# alcometer.net
KiCad netlist of a schematic drawn in EAGLE
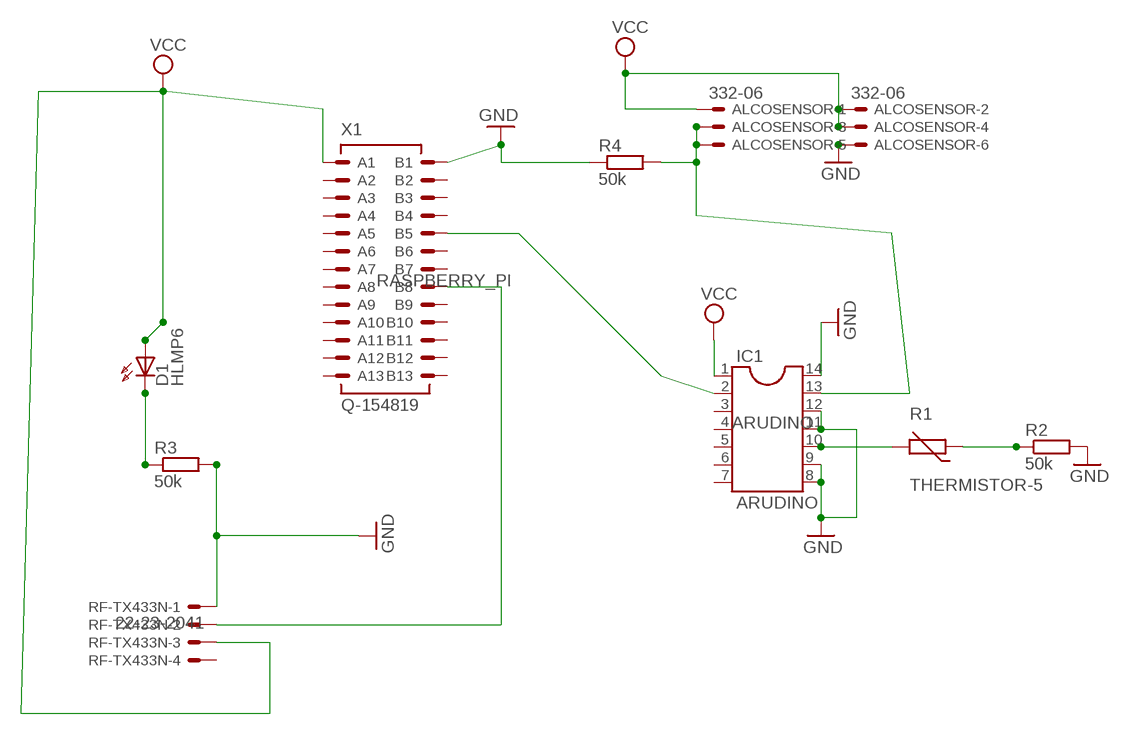
[diagram p0: schematic, sheet 1]

(export (version "E")
  (design (tool "Eeschema 10.0.6"))
  (components
    (comp (ref "ALCOSENSOR")
      (value "332-06")
      (footprint "eagle-import:332-06")
      (libsource (lib "eagle-import") (part "332-06"))
    )
    (comp (ref "D1")
      (value "HLMP6")
      (footprint "eagle-import:HLMP6")
      (fields (field (name "MF") "AGILENT TECHNOLOGIES") (field (name "MPN") "HLMP-6500"))
      (libsource (lib "eagle-import") (part "HLMP6"))
    )
    (comp (ref "IC1")
      (value "ARUDINO")
      (footprint "eagle-import:DIL14")
      (libsource (lib "eagle-import") (part "DIL14"))
    )
    (comp (ref "R1")
      (value "THERMISTOR-5")
      (footprint "eagle-import:R-5")
      (libsource (lib "eagle-import") (part "THERMISTOR-5"))
    )
    (comp (ref "R2")
      (value "50k")
      (footprint "eagle-import:0204_7")
      (libsource (lib "eagle-import") (part "R-EU_0204/7"))
    )
    (comp (ref "R3")
      (value "50k")
      (footprint "eagle-import:0204_7")
      (libsource (lib "eagle-import") (part "R-EU_0204/7"))
    )
    (comp (ref "R4")
      (value "50k")
      (footprint "eagle-import:0204_7")
      (libsource (lib "eagle-import") (part "R-EU_0204/7"))
    )
    (comp (ref "RF-TX433N")
      (value "22-23-2041")
      (footprint "eagle-import:22-23-2041")
      (fields (field (name "MF") "MOLEX"))
      (libsource (lib "eagle-import") (part "22-23-2041"))
    )
    (comp (ref "X1")
      (value "Q-154819")
      (footprint "eagle-import:154819")
      (libsource (lib "eagle-import") (part "Q-154819"))
    )
  )
  (nets
    (net (code "1") (name "GND") (class "Default")
      (node (ref "ALCOSENSOR") (pin "6") (pinfunction "S_6") (pintype "passive"))
      (node (ref "IC1") (pin "11") (pinfunction "11_11") (pintype "passive"))
      (node (ref "IC1") (pin "12") (pinfunction "12_12") (pintype "passive"))
      (node (ref "IC1") (pin "14") (pinfunction "14_14") (pintype "passive"))
      (node (ref "IC1") (pin "8") (pinfunction "8_8") (pintype "passive"))
      (node (ref "IC1") (pin "9") (pinfunction "9_9") (pintype "passive"))
      (node (ref "R2") (pin "2") (pinfunction "2_2") (pintype "passive"))
      (node (ref "R3") (pin "2") (pinfunction "2_2") (pintype "passive"))
      (node (ref "R4") (pin "1") (pinfunction "1_1") (pintype "passive"))
      (node (ref "RF-TX433N") (pin "1") (pinfunction "S_1") (pintype "passive"))
      (node (ref "X1") (pin "B1") (pinfunction "B1_B1") (pintype "passive"))
    )
    (net (code "2") (name "Net-(ALCOSENSORC-S)") (class "Default")
      (node (ref "ALCOSENSOR") (pin "3") (pinfunction "S_3") (pintype "passive"))
      (node (ref "ALCOSENSOR") (pin "5") (pinfunction "S_5") (pintype "passive"))
      (node (ref "IC1") (pin "13") (pinfunction "13_13") (pintype "passive"))
      (node (ref "R4") (pin "2") (pinfunction "2_2") (pintype "passive"))
    )
    (net (code "3") (name "Net-(D1-PadK)") (class "Default")
      (node (ref "D1") (pin "K") (pinfunction "K_K") (pintype "passive"))
      (node (ref "R3") (pin "1") (pinfunction "1_1") (pintype "passive"))
    )
    (net (code "4") (name "Net-(IC1-Pad2)") (class "Default")
      (node (ref "IC1") (pin "2") (pinfunction "2_2") (pintype "passive"))
      (node (ref "X1") (pin "B5") (pinfunction "B5_B5") (pintype "passive"))
    )
    (net (code "5") (name "Net-(IC1-Pad10)") (class "Default")
      (node (ref "IC1") (pin "10") (pinfunction "10_10") (pintype "passive"))
      (node (ref "R1") (pin "2") (pinfunction "2_2") (pintype "passive"))
    )
    (net (code "6") (name "Net-(R1-Pad1)") (class "Default")
      (node (ref "R1") (pin "1") (pinfunction "1_1") (pintype "passive"))
      (node (ref "R2") (pin "1") (pinfunction "1_1") (pintype "passive"))
    )
    (net (code "7") (name "Net-(RF-TX433NB-S)") (class "Default")
      (node (ref "RF-TX433N") (pin "2") (pinfunction "S_2") (pintype "passive"))
      (node (ref "X1") (pin "B8") (pinfunction "B8_B8") (pintype "passive"))
    )
    (net (code "8") (name "VCC") (class "Default")
      (node (ref "ALCOSENSOR") (pin "1") (pinfunction "S_1") (pintype "passive"))
      (node (ref "ALCOSENSOR") (pin "2") (pinfunction "S_2") (pintype "passive"))
      (node (ref "ALCOSENSOR") (pin "4") (pinfunction "S_4") (pintype "passive"))
      (node (ref "D1") (pin "A") (pinfunction "A_A") (pintype "passive"))
      (node (ref "IC1") (pin "1") (pinfunction "1_1") (pintype "passive"))
      (node (ref "RF-TX433N") (pin "3") (pinfunction "S_3") (pintype "passive"))
      (node (ref "X1") (pin "A1") (pinfunction "A1_A1") (pintype "passive"))
    )
    (net (code "9") (name "unconnected-(IC1-Pad3)") (class "Default")
      (node (ref "IC1") (pin "3") (pinfunction "3_3") (pintype "passive"))
    )
    (net (code "10") (name "unconnected-(IC1-Pad4)") (class "Default")
      (node (ref "IC1") (pin "4") (pinfunction "4_4") (pintype "passive"))
    )
    (net (code "11") (name "unconnected-(IC1-Pad5)") (class "Default")
      (node (ref "IC1") (pin "5") (pinfunction "5_5") (pintype "passive"))
    )
    (net (code "12") (name "unconnected-(IC1-Pad6)") (class "Default")
      (node (ref "IC1") (pin "6") (pinfunction "6_6") (pintype "passive"))
    )
    (net (code "13") (name "unconnected-(IC1-Pad7)") (class "Default")
      (node (ref "IC1") (pin "7") (pinfunction "7_7") (pintype "passive"))
    )
    (net (code "14") (name "unconnected-(RF-TX433ND-S-Pad4)") (class "Default")
      (node (ref "RF-TX433N") (pin "4") (pinfunction "S_4") (pintype "passive"))
    )
    (net (code "15") (name "unconnected-(X1-PadA2)") (class "Default")
      (node (ref "X1") (pin "A2") (pinfunction "A2_A2") (pintype "passive"))
    )
    (net (code "16") (name "unconnected-(X1-PadA3)") (class "Default")
      (node (ref "X1") (pin "A3") (pinfunction "A3_A3") (pintype "passive"))
    )
    (net (code "17") (name "unconnected-(X1-PadA4)") (class "Default")
      (node (ref "X1") (pin "A4") (pinfunction "A4_A4") (pintype "passive"))
    )
    (net (code "18") (name "unconnected-(X1-PadA5)") (class "Default")
      (node (ref "X1") (pin "A5") (pinfunction "A5_A5") (pintype "passive"))
    )
    (net (code "19") (name "unconnected-(X1-PadA6)") (class "Default")
      (node (ref "X1") (pin "A6") (pinfunction "A6_A6") (pintype "passive"))
    )
    (net (code "20") (name "unconnected-(X1-PadA7)") (class "Default")
      (node (ref "X1") (pin "A7") (pinfunction "A7_A7") (pintype "passive"))
    )
    (net (code "21") (name "unconnected-(X1-PadA8)") (class "Default")
      (node (ref "X1") (pin "A8") (pinfunction "A8_A8") (pintype "passive"))
    )
    (net (code "22") (name "unconnected-(X1-PadA9)") (class "Default")
      (node (ref "X1") (pin "A9") (pinfunction "A9_A9") (pintype "passive"))
    )
    (net (code "23") (name "unconnected-(X1-PadA10)") (class "Default")
      (node (ref "X1") (pin "A10") (pinfunction "A10_A10") (pintype "passive"))
    )
    (net (code "24") (name "unconnected-(X1-PadA11)") (class "Default")
      (node (ref "X1") (pin "A11") (pinfunction "A11_A11") (pintype "passive"))
    )
    (net (code "25") (name "unconnected-(X1-PadA12)") (class "Default")
      (node (ref "X1") (pin "A12") (pinfunction "A12_A12") (pintype "passive"))
    )
    (net (code "26") (name "unconnected-(X1-PadA13)") (class "Default")
      (node (ref "X1") (pin "A13") (pinfunction "A13_A13") (pintype "passive"))
    )
    (net (code "27") (name "unconnected-(X1-PadB2)") (class "Default")
      (node (ref "X1") (pin "B2") (pinfunction "B2_B2") (pintype "passive"))
    )
    (net (code "28") (name "unconnected-(X1-PadB3)") (class "Default")
      (node (ref "X1") (pin "B3") (pinfunction "B3_B3") (pintype "passive"))
    )
    (net (code "29") (name "unconnected-(X1-PadB4)") (class "Default")
      (node (ref "X1") (pin "B4") (pinfunction "B4_B4") (pintype "passive"))
    )
    (net (code "30") (name "unconnected-(X1-PadB6)") (class "Default")
      (node (ref "X1") (pin "B6") (pinfunction "B6_B6") (pintype "passive"))
    )
    (net (code "31") (name "unconnected-(X1-PadB7)") (class "Default")
      (node (ref "X1") (pin "B7") (pinfunction "B7_B7") (pintype "passive"))
    )
    (net (code "32") (name "unconnected-(X1-PadB9)") (class "Default")
      (node (ref "X1") (pin "B9") (pinfunction "B9_B9") (pintype "passive"))
    )
    (net (code "33") (name "unconnected-(X1-PadB10)") (class "Default")
      (node (ref "X1") (pin "B10") (pinfunction "B10_B10") (pintype "passive"))
    )
    (net (code "34") (name "unconnected-(X1-PadB11)") (class "Default")
      (node (ref "X1") (pin "B11") (pinfunction "B11_B11") (pintype "passive"))
    )
    (net (code "35") (name "unconnected-(X1-PadB12)") (class "Default")
      (node (ref "X1") (pin "B12") (pinfunction "B12_B12") (pintype "passive"))
    )
    (net (code "36") (name "unconnected-(X1-PadB13)") (class "Default")
      (node (ref "X1") (pin "B13") (pinfunction "B13_B13") (pintype "passive"))
    )
  )
)
